# EOG_FRONT_END.net
KiCad netlist of a schematic drawn in Altium Designer
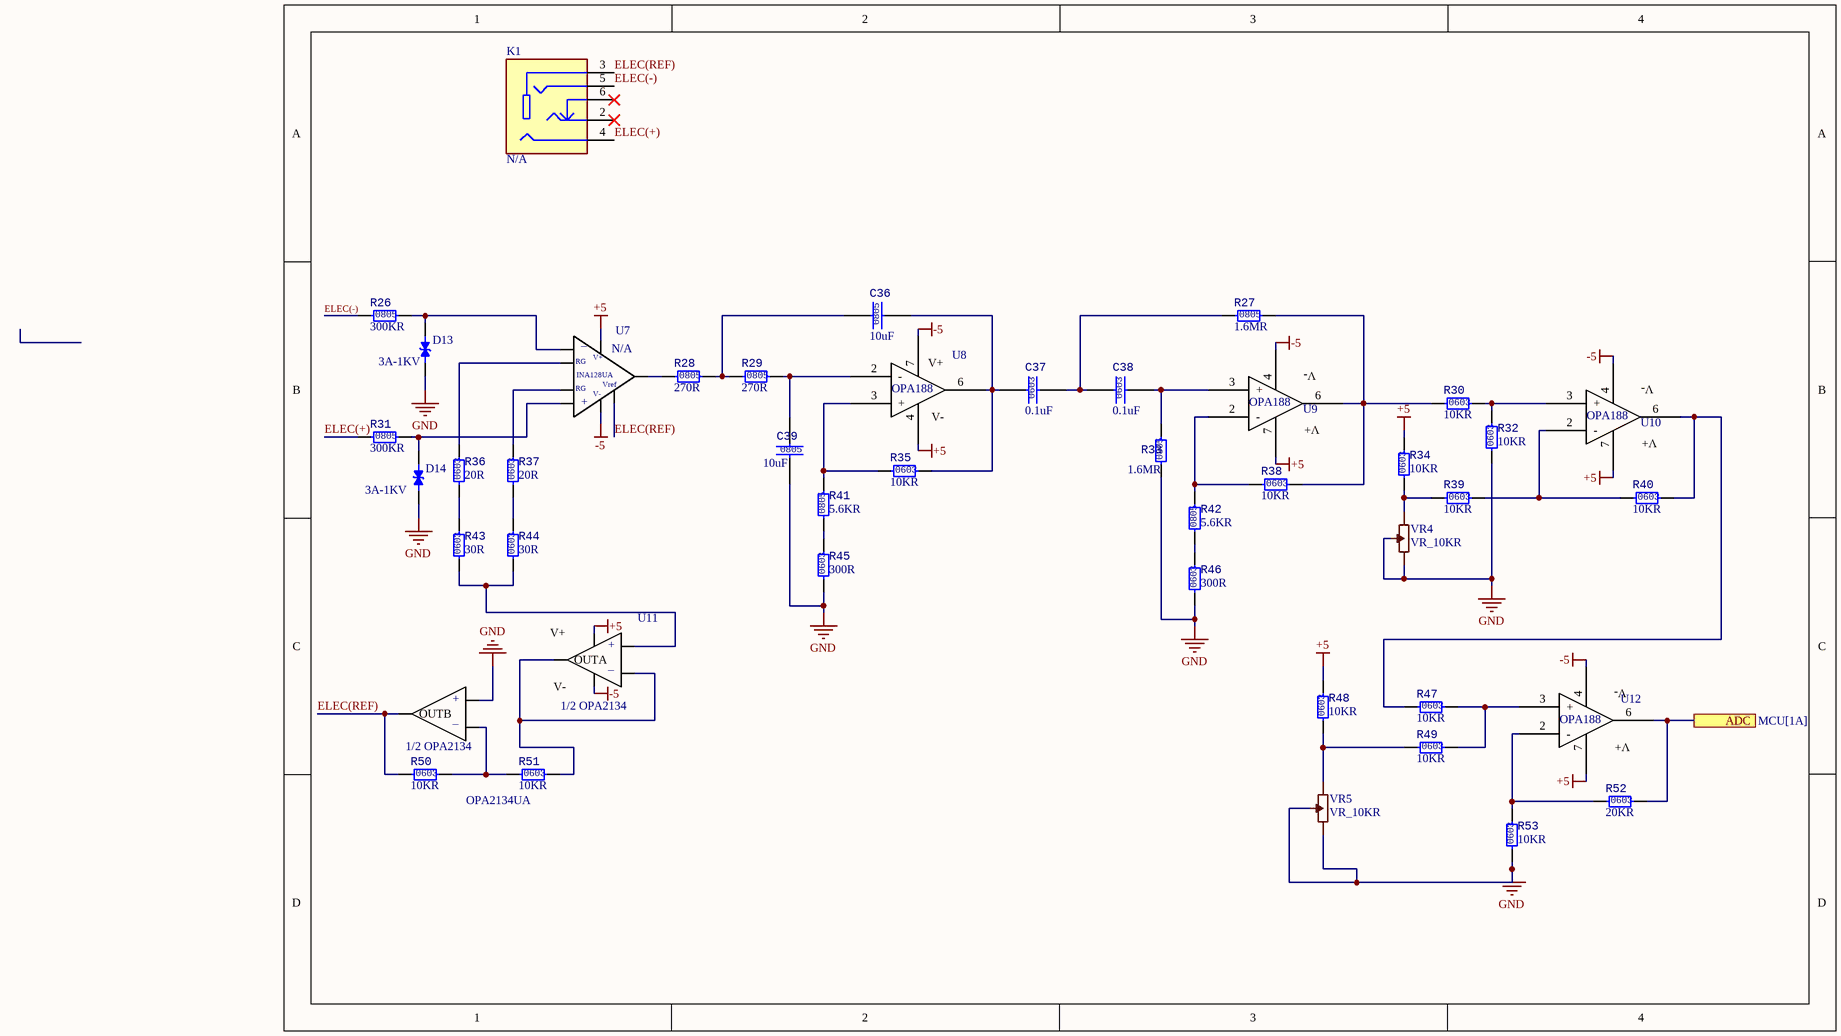
[diagram p0: EOG_FRONT_END.SchDoc]

(export (version "E")
  (design (tool "Eeschema 10.0.6"))
  (components
    (comp (ref "C36")
      (value "10uF")
      (footprint "CAPCER 0603 SMD")
      (description "CAPACITOR SMD 10uF 25V 10% 0805")
      (fields (field (name "SIZE") "0805") (field (name "TOLERANCE") "10%"))
      (libsource (lib "Database_Libs1") (part "CAPACITOR"))
    )
    (comp (ref "C37")
      (value "0.1uF")
      (footprint "CAPCER 0805 SMD")
      (description "CAPACITOR SMD 0.1uF 50V 10% 0603")
      (fields (field (name "SIZE") "0603") (field (name "TOLERANCE") "10%"))
      (libsource (lib "Database_Libs1") (part "CAPACITOR"))
    )
    (comp (ref "C38")
      (value "0.1uF")
      (footprint "CAPCER 0805 SMD")
      (description "CAPACITOR SMD 0.1uF 50V 10% 0603")
      (fields (field (name "SIZE") "0603") (field (name "TOLERANCE") "10%"))
      (libsource (lib "Database_Libs1") (part "CAPACITOR"))
    )
    (comp (ref "C39")
      (value "10uF")
      (footprint "CAPCER 0603 SMD")
      (description "CAPACITOR SMD 10uF 25V 10% 0805")
      (fields (field (name "SIZE") "0805") (field (name "TOLERANCE") "10%"))
      (libsource (lib "Database_Libs1") (part "CAPACITOR"))
    )
    (comp (ref "D13")
      (value "3A-1KV")
      (footprint "DO-214AC")
      (description "TVS DIODE 5VWM 9.2VC SMA")
      (fields (field (name "Comment") "SMAJ5.0"))
      (libsource (lib "Database_Libs1") (part "SMAJ5.0"))
    )
    (comp (ref "D14")
      (value "3A-1KV")
      (footprint "DO-214AC")
      (description "TVS DIODE 5VWM 9.2VC SMA")
      (fields (field (name "Comment") "SMAJ5.0"))
      (libsource (lib "Database_Libs1") (part "SMAJ5.0"))
    )
    (comp (ref "K1")
      (value "N/A")
      (footprint "PJ-327A")
      (description "PJ-327A Cổng Audio 3.5mm 3 Cực 5 Chân Dán SMD")
      (fields (field (name "Comment") "JACK_3.5_5P"))
      (libsource (lib "Database_Libs1") (part "PJ-327A-5P"))
    )
    (comp (ref "R26")
      (value "300KR")
      (footprint "RESC 0805 SMD")
      (description "RESISTOR SMD 300KR OHM 5% 125mW 0805")
      (fields (field (name "SIZE") "0805") (field (name "TOLERANCE") "5%"))
      (libsource (lib "") (part "RESISTOR_1"))
    )
    (comp (ref "R27")
      (value "1.6MR")
      (footprint "RESC 0805 SMD")
      (description "RESISTOR SMD 1.6MR OHM 5% 125mW 0805")
      (fields (field (name "SIZE") "0805") (field (name "TOLERANCE") "5%"))
      (libsource (lib "") (part "RESISTOR_1"))
    )
    (comp (ref "R28")
      (value "270R")
      (footprint "RESC 0805 SMD")
      (description "RESISTOR SMD 270R OHM 5% 125mW 0805")
      (fields (field (name "SIZE") "0805") (field (name "TOLERANCE") "5%"))
      (libsource (lib "") (part "RESISTOR_1"))
    )
    (comp (ref "R29")
      (value "270R")
      (footprint "RESC 0805 SMD")
      (description "RESISTOR SMD 270R OHM 5% 125mW 0805")
      (fields (field (name "SIZE") "0805") (field (name "TOLERANCE") "5%"))
      (libsource (lib "") (part "RESISTOR_1"))
    )
    (comp (ref "R30")
      (value "10KR")
      (footprint "RESC 0603(1608) SMD")
      (description "RESISTOR SMD 10KR OHM 1% 100mW 0603")
      (fields (field (name "SIZE") "0603") (field (name "TOLERANCE") "1%"))
      (libsource (lib "") (part "RESISTOR_1"))
    )
    (comp (ref "R31")
      (value "300KR")
      (footprint "RESC 0805 SMD")
      (description "RESISTOR SMD 300KR OHM 5% 125mW 0805")
      (fields (field (name "SIZE") "0805") (field (name "TOLERANCE") "5%"))
      (libsource (lib "") (part "RESISTOR_1"))
    )
    (comp (ref "R32")
      (value "10KR")
      (footprint "RESC 0603(1608) SMD")
      (description "RESISTOR SMD 10KR OHM 1% 100mW 0603")
      (fields (field (name "SIZE") "0603") (field (name "TOLERANCE") "1%"))
      (libsource (lib "Database_Libs1") (part "RESISTOR"))
    )
    (comp (ref "R33")
      (value "1.6MR")
      (footprint "RESC 0805 SMD")
      (description "RESISTOR SMD 1.6MR OHM 5% 125mW 0805")
      (fields (field (name "SIZE") "0805") (field (name "TOLERANCE") "5%"))
      (libsource (lib "Database_Libs1") (part "RESISTOR"))
    )
    (comp (ref "R34")
      (value "10KR")
      (footprint "RESC 0603(1608) SMD")
      (description "RESISTOR SMD 10KR OHM 1% 100mW 0603")
      (fields (field (name "SIZE") "0603") (field (name "TOLERANCE") "1%"))
      (libsource (lib "Database_Libs1") (part "RESISTOR"))
    )
    (comp (ref "R35")
      (value "10KR")
      (footprint "RESC 0603(1608) SMD")
      (description "RESISTOR SMD 10KR OHM 1% 100mW 0603")
      (fields (field (name "SIZE") "0603") (field (name "TOLERANCE") "1%"))
      (libsource (lib "") (part "RESISTOR_1"))
    )
    (comp (ref "R36")
      (value "20R")
      (footprint "RESC 0603(1608) SMD")
      (description "RESISTOR SMD 510R OHM 1% 100mW 0603")
      (fields (field (name "SIZE") "0603") (field (name "TOLERANCE") "1%") (field (name "Comment") "510R"))
      (libsource (lib "Database_Libs1") (part "RESISTOR"))
    )
    (comp (ref "R37")
      (value "20R")
      (footprint "RESC 0603(1608) SMD")
      (description "RESISTOR SMD 510R OHM 1% 100mW 0603")
      (fields (field (name "SIZE") "0603") (field (name "TOLERANCE") "1%") (field (name "Comment") "510R"))
      (libsource (lib "Database_Libs1") (part "RESISTOR"))
    )
    (comp (ref "R38")
      (value "10KR")
      (footprint "RESC 0603(1608) SMD")
      (description "RESISTOR SMD 10KR OHM 1% 100mW 0603")
      (fields (field (name "SIZE") "0603") (field (name "TOLERANCE") "1%"))
      (libsource (lib "") (part "RESISTOR_1"))
    )
    (comp (ref "R39")
      (value "10KR")
      (footprint "RESC 0603(1608) SMD")
      (description "RESISTOR SMD 10KR OHM 1% 100mW 0603")
      (fields (field (name "SIZE") "0603") (field (name "TOLERANCE") "1%"))
      (libsource (lib "") (part "RESISTOR_1"))
    )
    (comp (ref "R40")
      (value "10KR")
      (footprint "RESC 0603(1608) SMD")
      (description "RESISTOR SMD 10KR OHM 1% 100mW 0603")
      (fields (field (name "SIZE") "0603") (field (name "TOLERANCE") "1%"))
      (libsource (lib "") (part "RESISTOR_1"))
    )
    (comp (ref "R41")
      (value "5.6KR")
      (footprint "RESC 0805 SMD")
      (description "RESISTOR SMD 5.6KR OHM 1% 125mW 0805")
      (fields (field (name "SIZE") "0805") (field (name "TOLERANCE") "1%"))
      (libsource (lib "Database_Libs1") (part "RESISTOR"))
    )
    (comp (ref "R42")
      (value "5.6KR")
      (footprint "RESC 0805 SMD")
      (description "RESISTOR SMD 5.6KR OHM 1% 125mW 0805")
      (fields (field (name "SIZE") "0805") (field (name "TOLERANCE") "1%"))
      (libsource (lib "Database_Libs1") (part "RESISTOR"))
    )
    (comp (ref "R43")
      (value "30R")
      (footprint "RESC 0603(1608) SMD")
      (description "RESISTOR SMD 12KR OHM 1% 100mW 0603")
      (fields (field (name "SIZE") "0603") (field (name "TOLERANCE") "1%") (field (name "Comment") "12KR"))
      (libsource (lib "Database_Libs1") (part "RESISTOR"))
    )
    (comp (ref "R44")
      (value "30R")
      (footprint "RESC 0603(1608) SMD")
      (description "RESISTOR SMD 12KR OHM 1% 100mW 0603")
      (fields (field (name "SIZE") "0603") (field (name "TOLERANCE") "1%") (field (name "Comment") "12KR"))
      (libsource (lib "Database_Libs1") (part "RESISTOR"))
    )
    (comp (ref "R45")
      (value "300R")
      (footprint "RESC 0603(1608) SMD")
      (description "RESISTOR SMD 300R OHM 1% 125mW 0603")
      (fields (field (name "SIZE") "0603") (field (name "TOLERANCE") "1%"))
      (libsource (lib "Database_Libs1") (part "RESISTOR"))
    )
    (comp (ref "R46")
      (value "300R")
      (footprint "RESC 0603(1608) SMD")
      (description "RESISTOR SMD 300R OHM 1% 125mW 0603")
      (fields (field (name "SIZE") "0603") (field (name "TOLERANCE") "1%"))
      (libsource (lib "Database_Libs1") (part "RESISTOR"))
    )
    (comp (ref "R47")
      (value "10KR")
      (footprint "RESC 0603(1608) SMD")
      (description "RESISTOR SMD 10KR OHM 1% 100mW 0603")
      (fields (field (name "SIZE") "0603") (field (name "TOLERANCE") "1%"))
      (libsource (lib "") (part "RESISTOR_1"))
    )
    (comp (ref "R48")
      (value "10KR")
      (footprint "RESC 0603(1608) SMD")
      (description "RESISTOR SMD 10KR OHM 1% 100mW 0603")
      (fields (field (name "SIZE") "0603") (field (name "TOLERANCE") "1%"))
      (libsource (lib "Database_Libs1") (part "RESISTOR"))
    )
    (comp (ref "R49")
      (value "10KR")
      (footprint "RESC 0603(1608) SMD")
      (description "RESISTOR SMD 10KR OHM 1% 100mW 0603")
      (fields (field (name "SIZE") "0603") (field (name "TOLERANCE") "1%"))
      (libsource (lib "") (part "RESISTOR_1"))
    )
    (comp (ref "R50")
      (value "10KR")
      (footprint "RESC 0603(1608) SMD")
      (description "RESISTOR SMD 10KR OHM 1% 100mW 0603")
      (fields (field (name "SIZE") "0603") (field (name "TOLERANCE") "1%"))
      (libsource (lib "") (part "RESISTOR_1"))
    )
    (comp (ref "R51")
      (value "10KR")
      (footprint "RESC 0603(1608) SMD")
      (description "RESISTOR SMD 10KR OHM 1% 100mW 0603")
      (fields (field (name "SIZE") "0603") (field (name "TOLERANCE") "1%"))
      (libsource (lib "") (part "RESISTOR_1"))
    )
    (comp (ref "R52")
      (value "20KR")
      (footprint "RESC 0603(1608) SMD")
      (description "RESISTOR SMD 10KR OHM 1% 100mW 0603")
      (fields (field (name "SIZE") "0603") (field (name "TOLERANCE") "1%") (field (name "Comment") "10KR"))
      (libsource (lib "") (part "RESISTOR_1"))
    )
    (comp (ref "R53")
      (value "10KR")
      (footprint "RESC 0603(1608) SMD")
      (description "RESISTOR SMD 10KR OHM 1% 100mW 0603")
      (fields (field (name "SIZE") "0603") (field (name "TOLERANCE") "1%"))
      (libsource (lib "Database_Libs1") (part "RESISTOR"))
    )
    (comp (ref "U7")
      (value "N/A")
      (footprint "8-SOIC")
      (description "Instrumentation Amplifier 1 Circuit 8-SOIC")
      (fields (field (name "Comment") "INA128UA"))
      (libsource (lib "Database_Libs1") (part "INA128UA"))
    )
    (comp (ref "U8")
      (value "OPA188")
      (footprint "8-SOIC-OPA")
      (description "Zero-Drift Amplifier 1 Circuit Rail-to-Rail 8-SOIC")
      (fields (field (name "Comment") "OPA188AID"))
      (libsource (lib "Database_Libs1") (part "OPA188AID"))
    )
    (comp (ref "U9")
      (value "OPA188")
      (footprint "8-SOIC-OPA")
      (description "Zero-Drift Amplifier 1 Circuit Rail-to-Rail 8-SOIC")
      (fields (field (name "Comment") "OPA188AID"))
      (libsource (lib "Database_Libs1") (part "OPA188AID"))
    )
    (comp (ref "U10")
      (value "OPA188")
      (footprint "8-SOIC-OPA")
      (description "Zero-Drift Amplifier 1 Circuit Rail-to-Rail 8-SOIC")
      (fields (field (name "Comment") "OPA188AID"))
      (libsource (lib "Database_Libs1") (part "OPA188AID"))
    )
    (comp (ref "U11")
      (value "OPA2134UA")
      (footprint "8-SOIC-OPA")
      (description "IC AUDIO 2 CIRCUIT 8SOIC")
      (libsource (lib "Database_Libs1") (part "OPA2134UA"))
    )
    (comp (ref "U12")
      (value "OPA188")
      (footprint "8-SOIC-OPA")
      (description "Zero-Drift Amplifier 1 Circuit Rail-to-Rail 8-SOIC")
      (fields (field (name "Comment") "OPA188AID"))
      (libsource (lib "Database_Libs1") (part "OPA188AID"))
    )
    (comp (ref "VR4")
      (value "VR_10KR")
      (footprint "EVM3E")
      (description "EVM3E-103 Biến Trở 10 KOhm Nút Áo SMD 0.15W")
      (fields (field (name "TOLERANCE") "20%"))
      (libsource (lib "Database_Libs1") (part "VRES"))
    )
    (comp (ref "VR5")
      (value "VR_10KR")
      (footprint "EVM3E")
      (description "EVM3E-103 Biến Trở 10 KOhm Nút Áo SMD 0.15W")
      (fields (field (name "TOLERANCE") "20%"))
      (libsource (lib "Database_Libs1") (part "VRES"))
    )
  )
  (nets
    (net (code "1") (name "+5") (class "Default")
      (node (ref "R34") (pin "2") (pinfunction "2_2") (pintype "passive"))
      (node (ref "R48") (pin "2") (pinfunction "2_2") (pintype "passive"))
      (node (ref "U10") (pin "7") (pinfunction "VCC_7") (pintype "passive"))
      (node (ref "U11") (pin "8") (pinfunction "V+_8") (pintype "passive"))
      (node (ref "U12") (pin "7") (pinfunction "VCC_7") (pintype "passive"))
      (node (ref "U7") (pin "7") (pinfunction "9_7") (pintype "passive"))
      (node (ref "U8") (pin "4") (pinfunction "GND_4") (pintype "passive"))
      (node (ref "U9") (pin "7") (pinfunction "VCC_7") (pintype "passive"))
    )
    (net (code "2") (name "-5") (class "Default")
      (node (ref "U10") (pin "4") (pinfunction "GND_4") (pintype "passive"))
      (node (ref "U11") (pin "4") (pinfunction "V-_4") (pintype "passive"))
      (node (ref "U12") (pin "4") (pinfunction "GND_4") (pintype "passive"))
      (node (ref "U7") (pin "4") (pinfunction "10_4") (pintype "passive"))
      (node (ref "U8") (pin "7") (pinfunction "VCC_7") (pintype "passive"))
      (node (ref "U9") (pin "4") (pinfunction "GND_4") (pintype "passive"))
    )
    (net (code "3") (name "/ADC") (class "Default")
      (node (ref "R52") (pin "2") (pinfunction "2_2") (pintype "passive"))
      (node (ref "U12") (pin "6") (pinfunction "OUT_1_6") (pintype "passive"))
    )
    (net (code "4") (name "/ELEC(+)") (class "Default")
      (node (ref "K1") (pin "4") (pinfunction "2_4") (pintype "passive"))
      (node (ref "R31") (pin "1") (pinfunction "1_1") (pintype "passive"))
    )
    (net (code "5") (name "/ELEC(-)") (class "Default")
      (node (ref "K1") (pin "5") (pinfunction "3_5") (pintype "passive"))
      (node (ref "R26") (pin "1") (pinfunction "1_1") (pintype "passive"))
    )
    (net (code "6") (name "/ELEC(REF)") (class "Default")
      (node (ref "K1") (pin "3") (pinfunction "1_3") (pintype "passive"))
      (node (ref "R50") (pin "1") (pinfunction "1_1") (pintype "passive"))
      (node (ref "U11") (pin "7") (pinfunction "OUTB_7") (pintype "passive"))
      (node (ref "U7") (pin "5") (pinfunction "11_5") (pintype "passive"))
    )
    (net (code "7") (name "GND") (class "Default")
      (node (ref "C39") (pin "2") (pinfunction "2_2") (pintype "passive"))
      (node (ref "D13") (pin "1") (pinfunction "1_1") (pintype "passive"))
      (node (ref "D14") (pin "1") (pinfunction "1_1") (pintype "passive"))
      (node (ref "R32") (pin "1") (pinfunction "1_1") (pintype "passive"))
      (node (ref "R33") (pin "1") (pinfunction "1_1") (pintype "passive"))
      (node (ref "R45") (pin "1") (pinfunction "1_1") (pintype "passive"))
      (node (ref "R46") (pin "1") (pinfunction "1_1") (pintype "passive"))
      (node (ref "R53") (pin "1") (pinfunction "1_1") (pintype "passive"))
      (node (ref "U11") (pin "5") (pinfunction "INB(+)_5") (pintype "passive"))
      (node (ref "VR4") (pin "1") (pinfunction "1_1") (pintype "passive"))
      (node (ref "VR4") (pin "2") (pinfunction "2_2") (pintype "passive"))
      (node (ref "VR5") (pin "1") (pinfunction "1_1") (pintype "passive"))
      (node (ref "VR5") (pin "2") (pinfunction "2_2") (pintype "passive"))
    )
    (net (code "8") (name "Net-(C36-Pad1)") (class "Default")
      (node (ref "C36") (pin "1") (pinfunction "1_1") (pintype "passive"))
      (node (ref "R28") (pin "2") (pinfunction "2_2") (pintype "passive"))
      (node (ref "R29") (pin "1") (pinfunction "1_1") (pintype "passive"))
    )
    (net (code "9") (name "Net-(C37-Pad2)") (class "Default")
      (node (ref "C37") (pin "2") (pinfunction "2_2") (pintype "passive"))
      (node (ref "C38") (pin "1") (pinfunction "1_1") (pintype "passive"))
      (node (ref "R27") (pin "1") (pinfunction "1_1") (pintype "passive"))
    )
    (net (code "10") (name "Net-(D13-Pad2)") (class "Default")
      (node (ref "D13") (pin "2") (pinfunction "2_2") (pintype "passive"))
      (node (ref "R26") (pin "2") (pinfunction "2_2") (pintype "passive"))
      (node (ref "U7") (pin "2") (pinfunction "10_2") (pintype "passive"))
    )
    (net (code "11") (name "Net-(R28-Pad1)") (class "Default")
      (node (ref "R28") (pin "1") (pinfunction "1_1") (pintype "passive"))
      (node (ref "U7") (pin "6") (pinfunction "9_6") (pintype "passive"))
    )
    (net (code "12") (name "Net-(R34-Pad1)") (class "Default")
      (node (ref "R34") (pin "1") (pinfunction "1_1") (pintype "passive"))
      (node (ref "R39") (pin "1") (pinfunction "1_1") (pintype "passive"))
      (node (ref "VR4") (pin "3") (pinfunction "3_3") (pintype "passive"))
    )
    (net (code "13") (name "Net-(R36-Pad1)") (class "Default")
      (node (ref "R36") (pin "1") (pinfunction "1_1") (pintype "passive"))
      (node (ref "R43") (pin "2") (pinfunction "2_2") (pintype "passive"))
    )
    (net (code "14") (name "Net-(R36-Pad2)") (class "Default")
      (node (ref "R36") (pin "2") (pinfunction "2_2") (pintype "passive"))
      (node (ref "U7") (pin "1") (pinfunction "11_1") (pintype "passive"))
    )
    (net (code "15") (name "Net-(R37-Pad1)") (class "Default")
      (node (ref "R37") (pin "1") (pinfunction "1_1") (pintype "passive"))
      (node (ref "R44") (pin "2") (pinfunction "2_2") (pintype "passive"))
    )
    (net (code "16") (name "Net-(R41-Pad1)") (class "Default")
      (node (ref "R41") (pin "1") (pinfunction "1_1") (pintype "passive"))
      (node (ref "R45") (pin "2") (pinfunction "2_2") (pintype "passive"))
    )
    (net (code "17") (name "Net-(R42-Pad1)") (class "Default")
      (node (ref "R42") (pin "1") (pinfunction "1_1") (pintype "passive"))
      (node (ref "R46") (pin "2") (pinfunction "2_2") (pintype "passive"))
    )
    (net (code "18") (name "Net-(R48-Pad1)") (class "Default")
      (node (ref "R48") (pin "1") (pinfunction "1_1") (pintype "passive"))
      (node (ref "R49") (pin "1") (pinfunction "1_1") (pintype "passive"))
      (node (ref "VR5") (pin "3") (pinfunction "3_3") (pintype "passive"))
    )
    (net (code "19") (name "Net-(U7-12)") (class "Default")
      (node (ref "R37") (pin "2") (pinfunction "2_2") (pintype "passive"))
      (node (ref "U7") (pin "8") (pinfunction "12_8") (pintype "passive"))
    )
    (net (code "20") (name "Net-(U7-13)") (class "Default")
      (node (ref "D14") (pin "2") (pinfunction "2_2") (pintype "passive"))
      (node (ref "R31") (pin "2") (pinfunction "2_2") (pintype "passive"))
      (node (ref "U7") (pin "3") (pinfunction "13_3") (pintype "passive"))
    )
    (net (code "21") (name "Net-(U8-+)") (class "Default")
      (node (ref "R35") (pin "1") (pinfunction "1_1") (pintype "passive"))
      (node (ref "R41") (pin "2") (pinfunction "2_2") (pintype "passive"))
      (node (ref "U8") (pin "3") (pinfunction "+_3") (pintype "passive"))
    )
    (net (code "22") (name "Net-(U8--)") (class "Default")
      (node (ref "C39") (pin "1") (pinfunction "1_1") (pintype "passive"))
      (node (ref "R29") (pin "2") (pinfunction "2_2") (pintype "passive"))
      (node (ref "U8") (pin "2") (pinfunction "-_2") (pintype "passive"))
    )
    (net (code "23") (name "Net-(U8-OUT_1)") (class "Default")
      (node (ref "C36") (pin "2") (pinfunction "2_2") (pintype "passive"))
      (node (ref "C37") (pin "1") (pinfunction "1_1") (pintype "passive"))
      (node (ref "R35") (pin "2") (pinfunction "2_2") (pintype "passive"))
      (node (ref "U8") (pin "6") (pinfunction "OUT_1_6") (pintype "passive"))
    )
    (net (code "24") (name "Net-(U9-+)") (class "Default")
      (node (ref "C38") (pin "2") (pinfunction "2_2") (pintype "passive"))
      (node (ref "R33") (pin "2") (pinfunction "2_2") (pintype "passive"))
      (node (ref "U9") (pin "3") (pinfunction "+_3") (pintype "passive"))
    )
    (net (code "25") (name "Net-(U9--)") (class "Default")
      (node (ref "R38") (pin "1") (pinfunction "1_1") (pintype "passive"))
      (node (ref "R42") (pin "2") (pinfunction "2_2") (pintype "passive"))
      (node (ref "U9") (pin "2") (pinfunction "-_2") (pintype "passive"))
    )
    (net (code "26") (name "Net-(U9-OUT_1)") (class "Default")
      (node (ref "R27") (pin "2") (pinfunction "2_2") (pintype "passive"))
      (node (ref "R30") (pin "1") (pinfunction "1_1") (pintype "passive"))
      (node (ref "R38") (pin "2") (pinfunction "2_2") (pintype "passive"))
      (node (ref "U9") (pin "6") (pinfunction "OUT_1_6") (pintype "passive"))
    )
    (net (code "27") (name "Net-(U10-+)") (class "Default")
      (node (ref "R30") (pin "2") (pinfunction "2_2") (pintype "passive"))
      (node (ref "R32") (pin "2") (pinfunction "2_2") (pintype "passive"))
      (node (ref "U10") (pin "3") (pinfunction "+_3") (pintype "passive"))
    )
    (net (code "28") (name "Net-(U10--)") (class "Default")
      (node (ref "R39") (pin "2") (pinfunction "2_2") (pintype "passive"))
      (node (ref "R40") (pin "1") (pinfunction "1_1") (pintype "passive"))
      (node (ref "U10") (pin "2") (pinfunction "-_2") (pintype "passive"))
    )
    (net (code "29") (name "Net-(U10-OUT_1)") (class "Default")
      (node (ref "R40") (pin "2") (pinfunction "2_2") (pintype "passive"))
      (node (ref "R47") (pin "1") (pinfunction "1_1") (pintype "passive"))
      (node (ref "U10") (pin "6") (pinfunction "OUT_1_6") (pintype "passive"))
    )
    (net (code "30") (name "Net-(U11-INA(+))") (class "Default")
      (node (ref "R43") (pin "1") (pinfunction "1_1") (pintype "passive"))
      (node (ref "R44") (pin "1") (pinfunction "1_1") (pintype "passive"))
      (node (ref "U11") (pin "2") (pinfunction "INA(+)_2") (pintype "passive"))
    )
    (net (code "31") (name "Net-(U11-INA(-))") (class "Default")
      (node (ref "R51") (pin "2") (pinfunction "2_2") (pintype "passive"))
      (node (ref "U11") (pin "1") (pinfunction "OUTA_1") (pintype "passive"))
      (node (ref "U11") (pin "3") (pinfunction "INA(-)_3") (pintype "passive"))
    )
    (net (code "32") (name "Net-(U11-INB(-))") (class "Default")
      (node (ref "R50") (pin "2") (pinfunction "2_2") (pintype "passive"))
      (node (ref "R51") (pin "1") (pinfunction "1_1") (pintype "passive"))
      (node (ref "U11") (pin "6") (pinfunction "INB(-)_6") (pintype "passive"))
    )
    (net (code "33") (name "Net-(U12-+)") (class "Default")
      (node (ref "R47") (pin "2") (pinfunction "2_2") (pintype "passive"))
      (node (ref "R49") (pin "2") (pinfunction "2_2") (pintype "passive"))
      (node (ref "U12") (pin "3") (pinfunction "+_3") (pintype "passive"))
    )
    (net (code "34") (name "Net-(U12--)") (class "Default")
      (node (ref "R52") (pin "1") (pinfunction "1_1") (pintype "passive"))
      (node (ref "R53") (pin "2") (pinfunction "2_2") (pintype "passive"))
      (node (ref "U12") (pin "2") (pinfunction "-_2") (pintype "passive"))
    )
    (net (code "35") (name "unconnected-(K1-3-Pad6)") (class "Default")
      (node (ref "K1") (pin "6") (pinfunction "3_6") (pintype "passive+no_connect"))
    )
    (net (code "36") (name "unconnected-(K1-Pad2)") (class "Default")
      (node (ref "K1") (pin "2") (pinfunction "2_2") (pintype "passive+no_connect"))
    )
  )
)
